# schematic.net
KiCad netlist of a schematic drawn in EAGLE
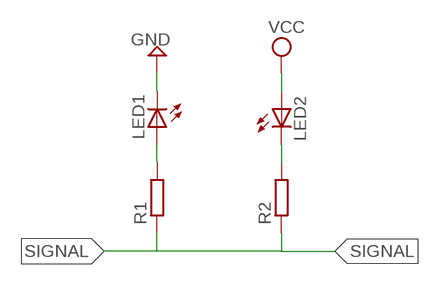
[diagram p0: schematic, sheet 1]

(export (version "E")
  (design (tool "Eeschema 10.0.6"))
  (components
    (comp (ref "LED1")
      (value "LED5MM")
      (footprint "eagle-import:LED5MM")
      (libsource (lib "eagle-import") (part "LED5MM"))
    )
    (comp (ref "LED2")
      (value "LED5MM")
      (footprint "eagle-import:LED5MM")
      (libsource (lib "eagle-import") (part "LED5MM"))
    )
    (comp (ref "R1")
      (value "R-EU_0207/10")
      (footprint "eagle-import:0207_10")
      (libsource (lib "eagle-import") (part "R-EU_0207/10"))
    )
    (comp (ref "R2")
      (value "R-EU_0207/10")
      (footprint "eagle-import:0207_10")
      (libsource (lib "eagle-import") (part "R-EU_0207/10"))
    )
  )
  (nets
    (net (code "1") (name "GND") (class "Default")
      (node (ref "LED1") (pin "K") (pinfunction "C_K") (pintype "passive"))
    )
    (net (code "2") (name "Net-(LED1-PadA)") (class "Default")
      (node (ref "LED1") (pin "A") (pinfunction "A_A") (pintype "passive"))
      (node (ref "R1") (pin "2") (pinfunction "2_2") (pintype "passive"))
    )
    (net (code "3") (name "Net-(LED2-C)") (class "Default")
      (node (ref "LED2") (pin "K") (pinfunction "C_K") (pintype "passive"))
      (node (ref "R2") (pin "2") (pinfunction "2_2") (pintype "passive"))
    )
    (net (code "4") (name "SIGNAL") (class "Default")
      (node (ref "R1") (pin "1") (pinfunction "1_1") (pintype "passive"))
      (node (ref "R2") (pin "1") (pinfunction "1_1") (pintype "passive"))
    )
    (net (code "5") (name "VCC") (class "Default")
      (node (ref "LED2") (pin "A") (pinfunction "A_A") (pintype "passive"))
    )
  )
)
